# Regulador5V.net
KiCad netlist of a schematic drawn in Altium Designer
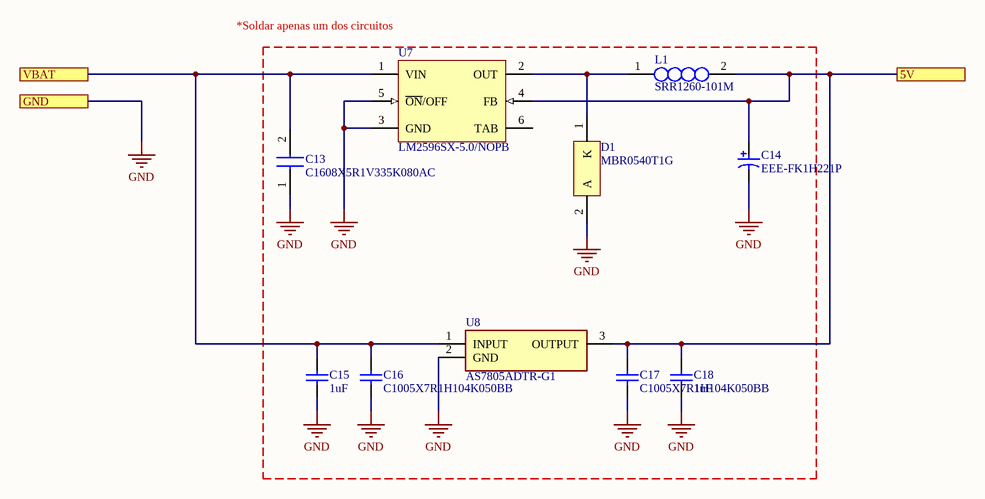
[diagram p0: Regulador5V.SchDoc]

(export (version "E")
  (design (tool "Eeschema 10.0.6"))
  (components
    (comp (ref "C13")
      (value "C1608X5R1V335K080AC")
      (footprint "CAPC1608X80N")
      (description "Capacitor 3.3uF")
      (fields (field (name "MOUSER PART NUMBER") "810-C1608X5R1V335KAC") (field (name "MANUFACTURER") "TDK"))
      (libsource (lib "*") (part "C1608X5R1V335K080AC"))
    )
    (comp (ref "C14")
      (value "EEE-FK1H221P")
      (footprint "PNSC-EEE-1HA221P_L")
      (fields (field (name "MANUFACTURER") "Panasonic"))
      (libsource (lib "Altium Content Vault") (part "CAP-P-2"))
    )
    (comp (ref "C15")
      (value "1uF")
      (footprint "CAPC1608X90X35ML10T15")
      (fields
        (field (name "MANUFACTURER") "Murata")
        (field (name "PART NUMBER") "GRM188R61H105KAALD")
        (field (name "TOLERANCE") "10%")
      )
      (libsource (lib "Altium Content Vault") (part "CAP"))
    )
    (comp (ref "C16")
      (value "C1005X7R1H104K050BB")
      (footprint "TDK-C1005-2_M")
      (description "Chip Capacitor, 0.1 uF, +/- 10%, 50 V, -55 to 125 degC, 0402(1005 Metric), RoHS, Tape and Reel")
      (fields
        (field (name "PCN PART NUMBER") "MLCCPartNumberChange30/Nov/2012")
        (field (name "TOLERANCE") "±10%")
      )
      (libsource (lib "Altium Content Vault") (part "CAP-NP-2"))
    )
    (comp (ref "C17")
      (value "C1005X7R1H104K050BB")
      (footprint "TDK-C1005-2_M")
      (description "Chip Capacitor, 0.1 uF, +/- 10%, 50 V, -55 to 125 degC, 0402(1005 Metric), RoHS, Tape and Reel")
      (fields
        (field (name "PCN PART NUMBER") "MLCCPartNumberChange30/Nov/2012")
        (field (name "TOLERANCE") "±10%")
      )
      (libsource (lib "Altium Content Vault") (part "CAP-NP-2"))
    )
    (comp (ref "C18")
      (value "1uF")
      (footprint "CAPC1608X90X35ML10T15")
      (fields
        (field (name "MANUFACTURER") "Murata")
        (field (name "PART NUMBER") "GRM188R61H105KAALD")
        (field (name "TOLERANCE") "10%")
      )
      (libsource (lib "Altium Content Vault") (part "CAP"))
    )
    (comp (ref "D1")
      (value "MBR0540T1G")
      (footprint "ONSC-SOD-123-2-425-04_V")
      (description "Schottky Power Rectifier, 2-Pin SOD-123, Pb-Free, Tape and Reel")
      (fields (field (name "MANUFACTURER") "On Semiconductor"))
      (libsource (lib "Altium Content Vault") (part "ONSC-D-K1A2-2_A"))
    )
    (comp (ref "L1")
      (value "SRR1260-101M")
      (footprint "*INDP125125X600N")
      (description "FIXED IND 100UH 1.7A 180 MOHM")
      (fields
        (field (name "MANUFACTURER_PART_NUMBER") "SRR1260-220M")
        (field (name "MOUSER PART NUMBER") "652-SRR1260-220M")
      )
      (libsource (lib "*") (part "SRR1260-220M"))
    )
    (comp (ref "U7")
      (value "LM2596SX-5.0/NOPB")
      (footprint "TS5B_M")
      (description "SIMPLE SWITCHER® Power Converter 150 KHz 3A Step-Down Voltage Regulator, 5-pin TO-263")
      (fields (field (name "MANUFACTURER") "Texas Instruments"))
      (libsource (lib "LM2596SX-5.0") (part "CMP-0069-00282-2"))
    )
    (comp (ref "U8")
      (value "AS7805ADTR-G1")
      (footprint "ZLDO1117K50TC")
      (description "Integrated Circuit")
      (fields (field (name "MOUSER PART NUMBER") "621-AS7805ADTR-G1"))
      (libsource (lib "*") (part "AS7805ADTR-G1"))
    )
  )
  (nets
    (net (code "1") (name "/5V") (class "Default")
      (node (ref "C14") (pin "1") (pinfunction "1_1") (pintype "passive"))
      (node (ref "C17") (pin "2") (pinfunction "2_2") (pintype "passive"))
      (node (ref "C18") (pin "2") (pinfunction "2_2") (pintype "passive"))
      (node (ref "L1") (pin "2") (pinfunction "2_2") (pintype "passive"))
      (node (ref "U7") (pin "4") (pinfunction "FB_4") (pintype "input"))
      (node (ref "U8") (pin "3") (pinfunction "OUTPUT_3") (pintype "passive"))
    )
    (net (code "2") (name "/VBAT") (class "Default")
      (node (ref "C13") (pin "2") (pinfunction "2_2") (pintype "passive"))
      (node (ref "C15") (pin "2") (pinfunction "2_2") (pintype "passive"))
      (node (ref "C16") (pin "2") (pinfunction "2_2") (pintype "passive"))
      (node (ref "U7") (pin "1") (pinfunction "VIN_1") (pintype "power_in"))
      (node (ref "U8") (pin "1") (pinfunction "INPUT_1") (pintype "passive"))
    )
    (net (code "3") (name "GND") (class "Default")
      (node (ref "C13") (pin "1") (pinfunction "1_1") (pintype "passive"))
      (node (ref "C14") (pin "2") (pinfunction "2_2") (pintype "passive"))
      (node (ref "C15") (pin "1") (pinfunction "1_1") (pintype "passive"))
      (node (ref "C16") (pin "1") (pinfunction "1_1") (pintype "passive"))
      (node (ref "C17") (pin "1") (pinfunction "1_1") (pintype "passive"))
      (node (ref "C18") (pin "1") (pinfunction "1_1") (pintype "passive"))
      (node (ref "D1") (pin "2") (pinfunction "A_2") (pintype "passive"))
      (node (ref "U7") (pin "3") (pinfunction "GND_3") (pintype "power_in"))
      (node (ref "U7") (pin "5") (pinfunction "~{ON}/OFF_5") (pintype "input"))
      (node (ref "U8") (pin "2") (pinfunction "GND_2") (pintype "passive"))
    )
    (net (code "4") (name "Net-(D1-K)") (class "Default")
      (node (ref "D1") (pin "1") (pinfunction "K_1") (pintype "passive"))
      (node (ref "L1") (pin "1") (pinfunction "1_1") (pintype "passive"))
      (node (ref "U7") (pin "2") (pinfunction "OUT_2") (pintype "power_in"))
    )
    (net (code "5") (name "unconnected-(U7-TAB-Pad6)") (class "Default")
      (node (ref "U7") (pin "6") (pinfunction "TAB_6") (pintype "power_in"))
    )
  )
)
